# auto-light-LGT8F328P_easyeda.net
KiCad netlist of a schematic drawn in EasyEDA
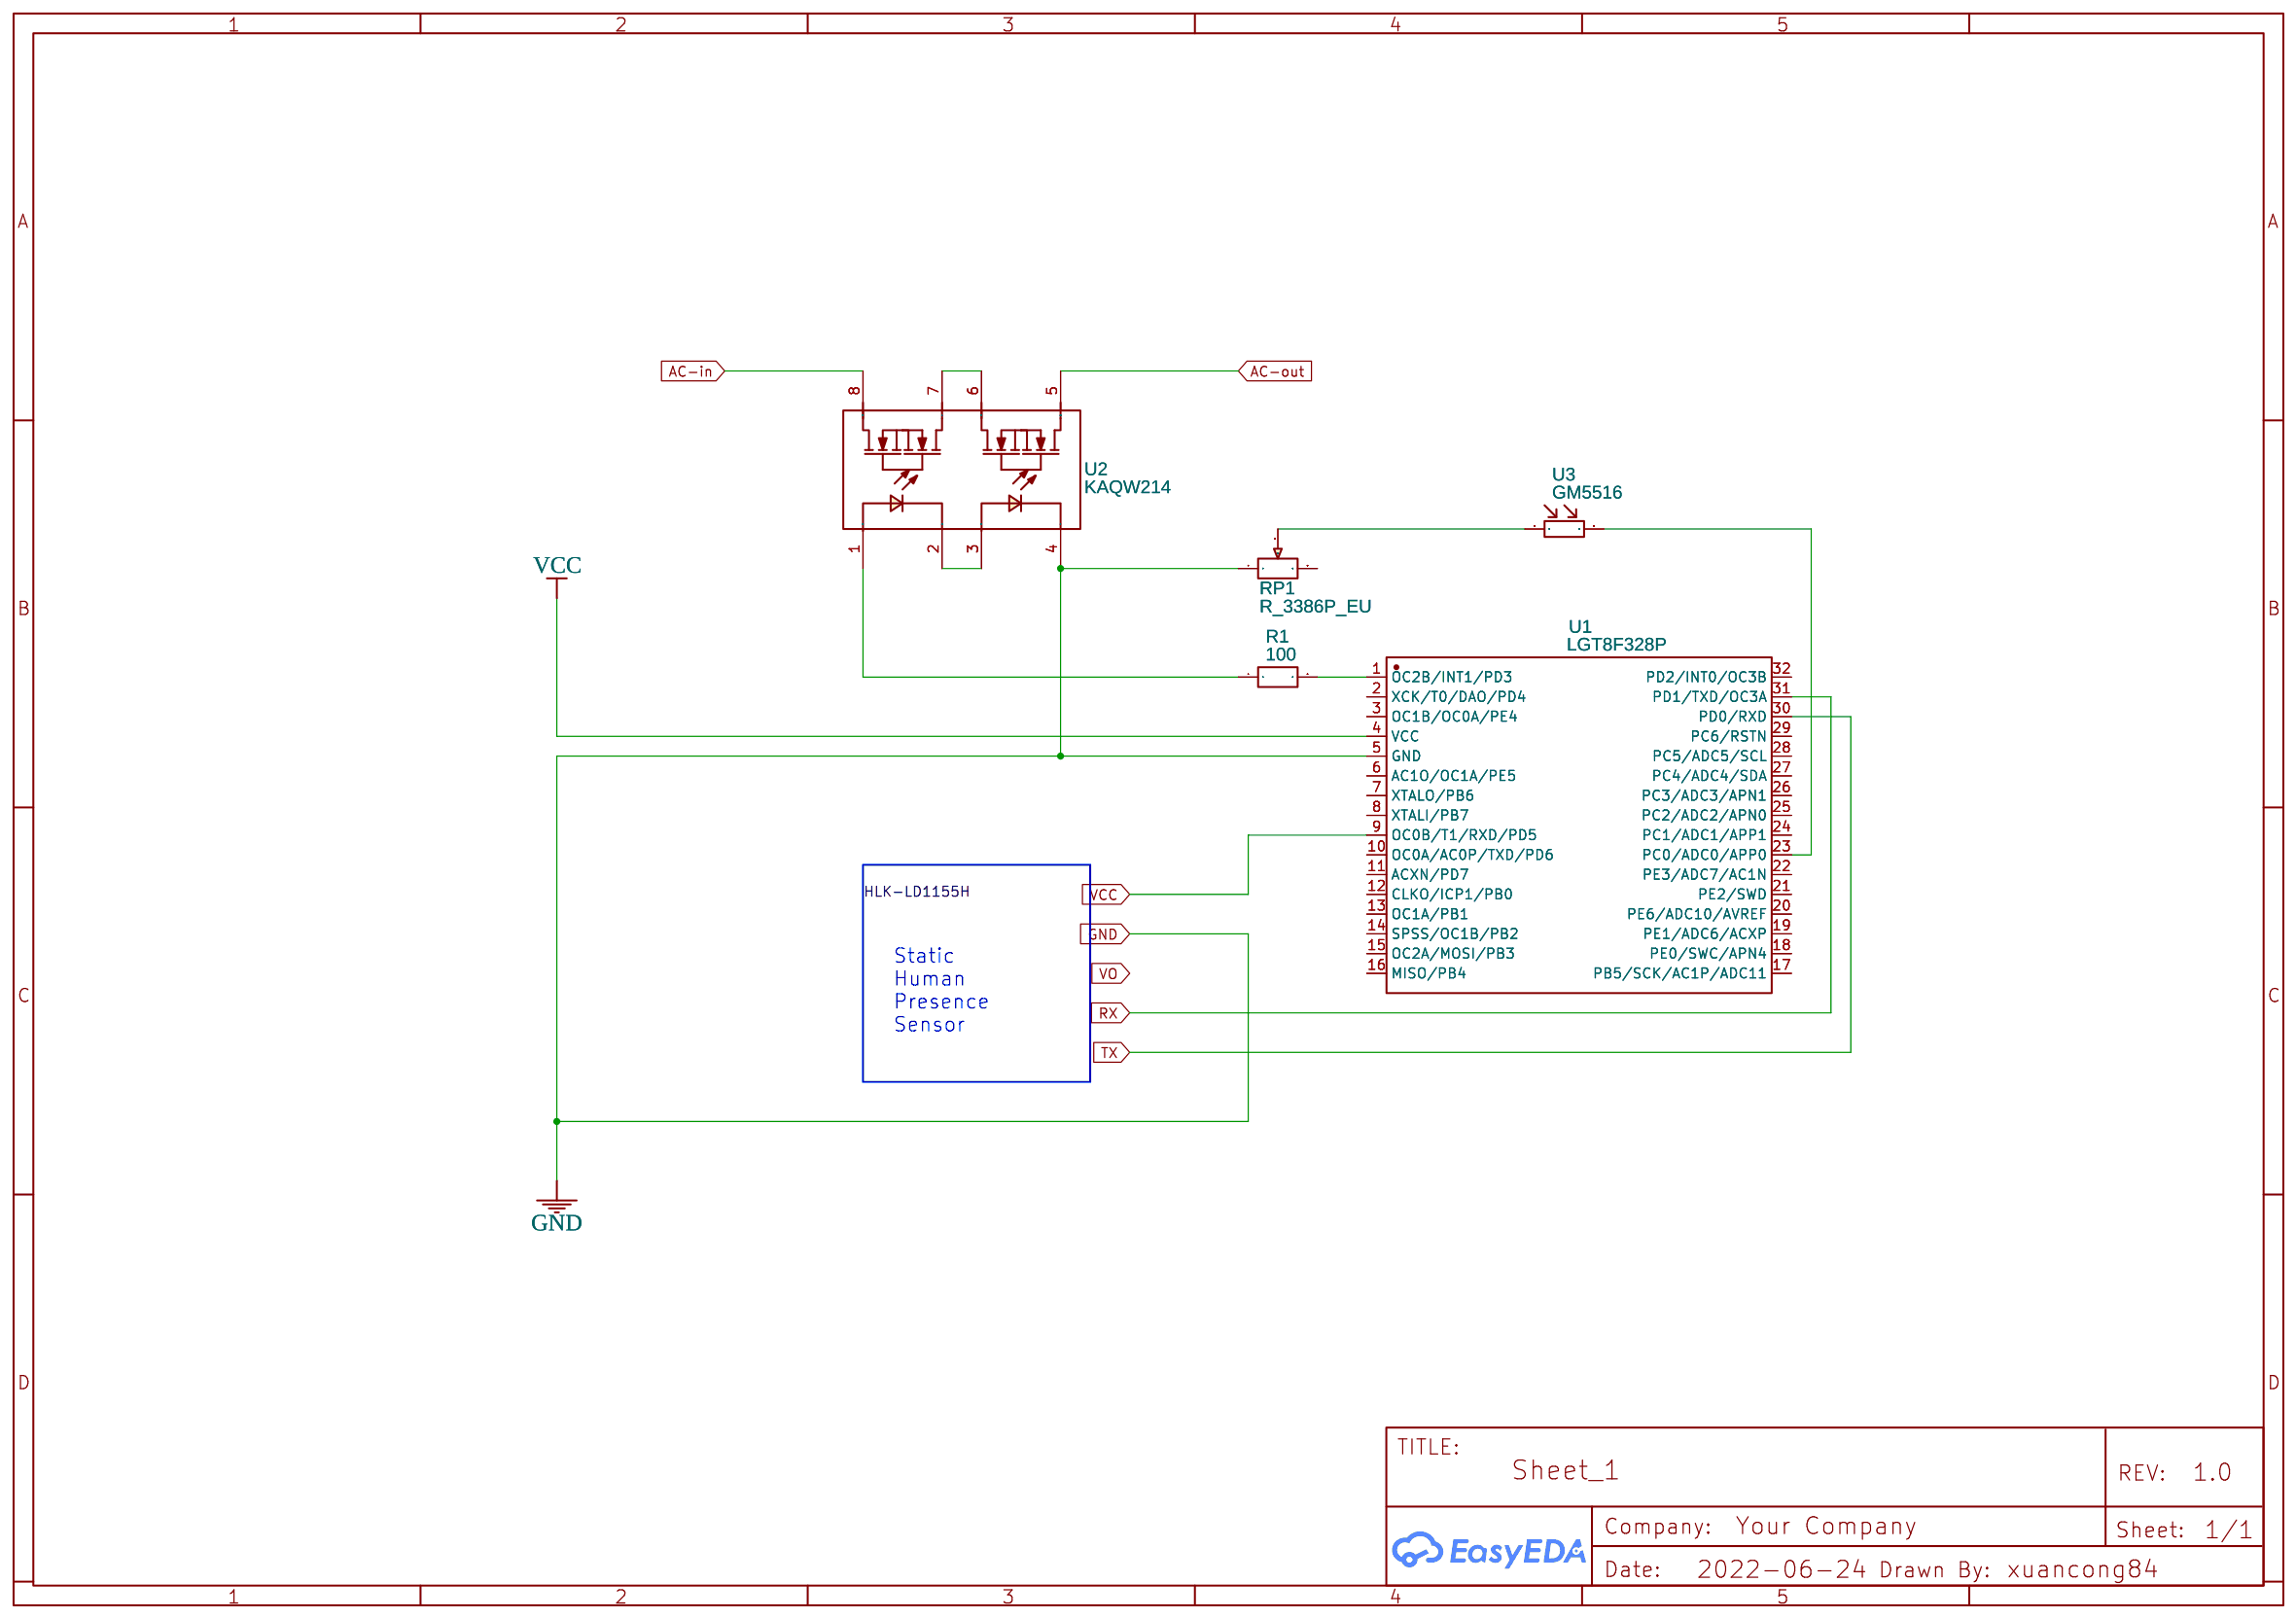
[diagram p0: schematic sheet]

(export (version "E")
  (design (tool "Eeschema 10.0.6"))
  (components
    (comp (ref "R1") (value "100") (libsource (lib "") (part "R_0603_EU")))
    (comp (ref "RP1") (value "R_3386P_EU") (libsource (lib "") (part "R_3386P_EU")))
    (comp (ref "U1")
      (value "LGT8F328P")
      (fields (field (name "BOM_Supplier Part") "C910803"))
      (libsource (lib "") (part "LGT8F328P"))
    )
    (comp (ref "U2")
      (value "KAQW214")
      (fields (field (name "BOM_Supplier Part") "C194714"))
      (libsource (lib "") (part "KAQW214"))
    )
    (comp (ref "U3")
      (value "GM5516")
      (fields (field (name "BOM_Supplier Part") "C2844193"))
      (libsource (lib "") (part "GM5516"))
    )
  )
  (nets
    (net (code "2") (name "AC-in") (class "Default")
      (node (ref "U2") (pin "8") (pinfunction "8_8") (pintype "unspecified"))
    )
    (net (code "3") (name "AC-out") (class "Default")
      (node (ref "U2") (pin "5") (pinfunction "5_5") (pintype "unspecified"))
    )
    (net (code "4") (name "GND") (class "Default")
      (node (ref "RP1") (pin "1") (pinfunction "1_1") (pintype "input"))
      (node (ref "U1") (pin "5") (pinfunction "GND_5") (pintype "unspecified"))
      (node (ref "U2") (pin "4") (pinfunction "4_4") (pintype "unspecified"))
    )
    (net (code "5") (name "Net-(R1-Pad1)") (class "Default")
      (node (ref "R1") (pin "1") (pinfunction "1_1") (pintype "unspecified"))
      (node (ref "U2") (pin "1") (pinfunction "1_1") (pintype "unspecified"))
    )
    (net (code "6") (name "Net-(RP1-Pad2)") (class "Default")
      (node (ref "RP1") (pin "2") (pinfunction "2_2") (pintype "input"))
      (node (ref "U3") (pin "1") (pinfunction "1_1") (pintype "input"))
    )
    (net (code "7") (name "Net-(U1-OC2B{slash}INT1{slash}PD3)") (class "Default")
      (node (ref "R1") (pin "2") (pinfunction "2_2") (pintype "unspecified"))
      (node (ref "U1") (pin "1") (pinfunction "OC2B/INT1/PD3_1") (pintype "unspecified"))
    )
    (net (code "8") (name "Net-(U1-PC0{slash}ADC0{slash}APP0)") (class "Default")
      (node (ref "U1") (pin "23") (pinfunction "PC0/ADC0/APP0_23") (pintype "unspecified"))
      (node (ref "U3") (pin "2") (pinfunction "2_2") (pintype "input"))
    )
    (net (code "9") (name "Net-(U2-Pad2)") (class "Default")
      (node (ref "U2") (pin "2") (pinfunction "2_2") (pintype "unspecified"))
      (node (ref "U2") (pin "3") (pinfunction "3_3") (pintype "unspecified"))
    )
    (net (code "10") (name "Net-(U2-Pad6)") (class "Default")
      (node (ref "U2") (pin "6") (pinfunction "6_6") (pintype "unspecified"))
      (node (ref "U2") (pin "7") (pinfunction "7_7") (pintype "unspecified"))
    )
    (net (code "11") (name "RX") (class "Default")
      (node (ref "U1") (pin "31") (pinfunction "PD1/TXD/OC3A_31") (pintype "unspecified"))
    )
    (net (code "12") (name "TX") (class "Default")
      (node (ref "U1") (pin "30") (pinfunction "PD0/RXD_30") (pintype "unspecified"))
    )
    (net (code "13") (name "VCC") (class "Default")
      (node (ref "U1") (pin "4") (pinfunction "VCC_4") (pintype "unspecified"))
      (node (ref "U1") (pin "9") (pinfunction "OC0B/T1/RXD/PD5_9") (pintype "unspecified"))
    )
    (net (code "15") (name "unconnected-(RP1-Pad3)") (class "Default")
      (node (ref "RP1") (pin "3") (pinfunction "3_3") (pintype "input"))
    )
    (net (code "16") (name "unconnected-(U1-AC1O{slash}OC1A{slash}PE5-Pad6)") (class "Default")
      (node (ref "U1") (pin "6") (pinfunction "AC1O/OC1A/PE5_6") (pintype "unspecified"))
    )
    (net (code "17") (name "unconnected-(U1-ACXN{slash}PD7-Pad11)") (class "Default")
      (node (ref "U1") (pin "11") (pinfunction "ACXN/PD7_11") (pintype "unspecified"))
    )
    (net (code "18") (name "unconnected-(U1-CLKO{slash}ICP1{slash}PB0-Pad12)") (class "Default")
      (node (ref "U1") (pin "12") (pinfunction "CLKO/ICP1/PB0_12") (pintype "unspecified"))
    )
    (net (code "19") (name "unconnected-(U1-MISO{slash}PB4-Pad16)") (class "Default")
      (node (ref "U1") (pin "16") (pinfunction "MISO/PB4_16") (pintype "unspecified"))
    )
    (net (code "20") (name "unconnected-(U1-OC0A{slash}AC0P{slash}TXD{slash}PD6-Pad10)") (class "Default")
      (node (ref "U1") (pin "10") (pinfunction "OC0A/AC0P/TXD/PD6_10") (pintype "unspecified"))
    )
    (net (code "21") (name "unconnected-(U1-OC1A{slash}PB1-Pad13)") (class "Default")
      (node (ref "U1") (pin "13") (pinfunction "OC1A/PB1_13") (pintype "unspecified"))
    )
    (net (code "22") (name "unconnected-(U1-OC1B{slash}OC0A{slash}PE4-Pad3)") (class "Default")
      (node (ref "U1") (pin "3") (pinfunction "OC1B/OC0A/PE4_3") (pintype "unspecified"))
    )
    (net (code "23") (name "unconnected-(U1-OC2A{slash}MOSI{slash}PB3-Pad15)") (class "Default")
      (node (ref "U1") (pin "15") (pinfunction "OC2A/MOSI/PB3_15") (pintype "unspecified"))
    )
    (net (code "24") (name "unconnected-(U1-PB5{slash}SCK{slash}AC1P{slash}ADC11-Pad17)") (class "Default")
      (node (ref "U1") (pin "17") (pinfunction "PB5/SCK/AC1P/ADC11_17") (pintype "unspecified"))
    )
    (net (code "25") (name "unconnected-(U1-PC1{slash}ADC1{slash}APP1-Pad24)") (class "Default")
      (node (ref "U1") (pin "24") (pinfunction "PC1/ADC1/APP1_24") (pintype "unspecified"))
    )
    (net (code "26") (name "unconnected-(U1-PC2{slash}ADC2{slash}APN0-Pad25)") (class "Default")
      (node (ref "U1") (pin "25") (pinfunction "PC2/ADC2/APN0_25") (pintype "unspecified"))
    )
    (net (code "27") (name "unconnected-(U1-PC3{slash}ADC3{slash}APN1-Pad26)") (class "Default")
      (node (ref "U1") (pin "26") (pinfunction "PC3/ADC3/APN1_26") (pintype "unspecified"))
    )
    (net (code "28") (name "unconnected-(U1-PC4{slash}ADC4{slash}SDA-Pad27)") (class "Default")
      (node (ref "U1") (pin "27") (pinfunction "PC4/ADC4/SDA_27") (pintype "unspecified"))
    )
    (net (code "29") (name "unconnected-(U1-PC5{slash}ADC5{slash}SCL-Pad28)") (class "Default")
      (node (ref "U1") (pin "28") (pinfunction "PC5/ADC5/SCL_28") (pintype "unspecified"))
    )
    (net (code "30") (name "unconnected-(U1-PC6{slash}RSTN-Pad29)") (class "Default")
      (node (ref "U1") (pin "29") (pinfunction "PC6/RSTN_29") (pintype "unspecified"))
    )
    (net (code "31") (name "unconnected-(U1-PD2{slash}INT0{slash}OC3B-Pad32)") (class "Default")
      (node (ref "U1") (pin "32") (pinfunction "PD2/INT0/OC3B_32") (pintype "unspecified"))
    )
    (net (code "32") (name "unconnected-(U1-PE0{slash}SWC{slash}APN4-Pad18)") (class "Default")
      (node (ref "U1") (pin "18") (pinfunction "PE0/SWC/APN4_18") (pintype "unspecified"))
    )
    (net (code "33") (name "unconnected-(U1-PE1{slash}ADC6{slash}ACXP-Pad19)") (class "Default")
      (node (ref "U1") (pin "19") (pinfunction "PE1/ADC6/ACXP_19") (pintype "unspecified"))
    )
    (net (code "34") (name "unconnected-(U1-PE2{slash}SWD-Pad21)") (class "Default")
      (node (ref "U1") (pin "21") (pinfunction "PE2/SWD_21") (pintype "unspecified"))
    )
    (net (code "35") (name "unconnected-(U1-PE3{slash}ADC7{slash}AC1N-Pad22)") (class "Default")
      (node (ref "U1") (pin "22") (pinfunction "PE3/ADC7/AC1N_22") (pintype "unspecified"))
    )
    (net (code "36") (name "unconnected-(U1-PE6{slash}ADC10{slash}AVREF-Pad20)") (class "Default")
      (node (ref "U1") (pin "20") (pinfunction "PE6/ADC10/AVREF_20") (pintype "unspecified"))
    )
    (net (code "37") (name "unconnected-(U1-SPSS{slash}OC1B{slash}PB2-Pad14)") (class "Default")
      (node (ref "U1") (pin "14") (pinfunction "SPSS/OC1B/PB2_14") (pintype "unspecified"))
    )
    (net (code "38") (name "unconnected-(U1-XCK{slash}T0{slash}DAO{slash}PD4-Pad2)") (class "Default")
      (node (ref "U1") (pin "2") (pinfunction "XCK/T0/DAO/PD4_2") (pintype "unspecified"))
    )
    (net (code "39") (name "unconnected-(U1-XTALI{slash}PB7-Pad8)") (class "Default")
      (node (ref "U1") (pin "8") (pinfunction "XTALI/PB7_8") (pintype "unspecified"))
    )
    (net (code "40") (name "unconnected-(U1-XTALO{slash}PB6-Pad7)") (class "Default")
      (node (ref "U1") (pin "7") (pinfunction "XTALO/PB6_7") (pintype "unspecified"))
    )
  )
)
